# collection.net
KiCad netlist of a schematic drawn in Altium Designer
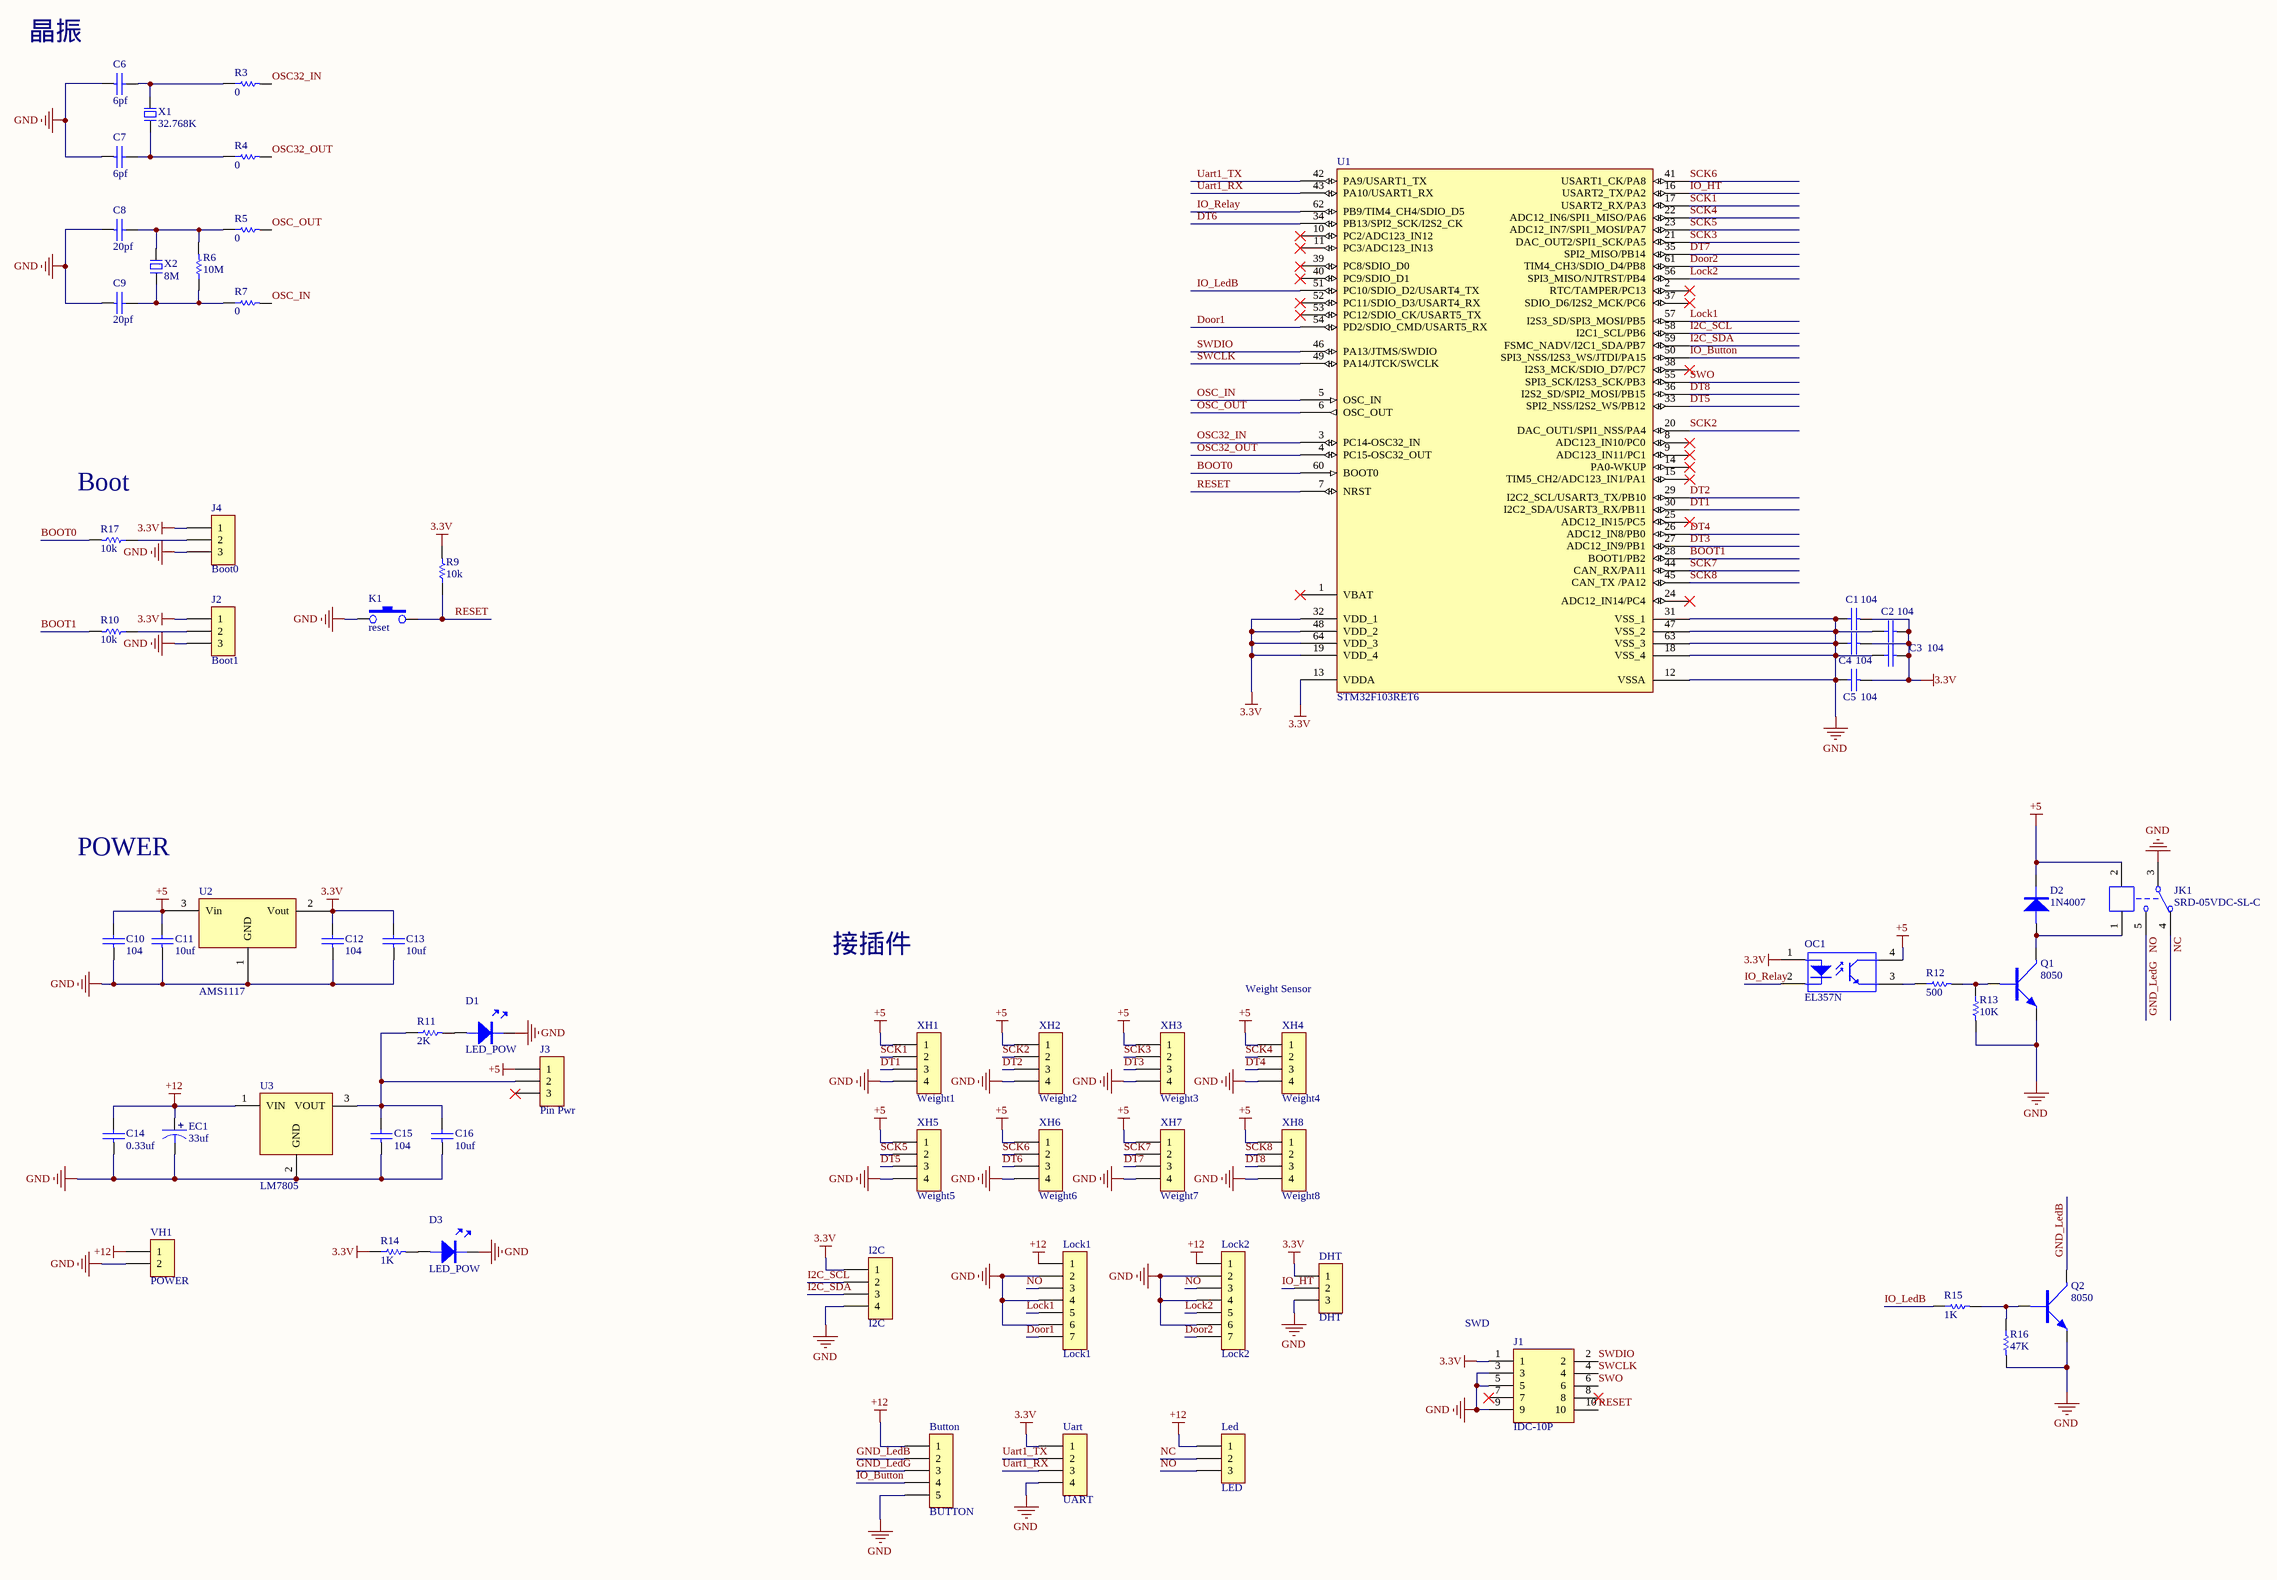
[diagram p0: collection.SchDoc]

(export (version "E")
  (design (tool "Eeschema 10.0.6"))
  (components
    (comp (ref "Button") (value "BUTTON") (footprint "XH5/2.54mm/90") (libsource (lib "XH，VH") (part "XH5")))
    (comp (ref "C1")
      (value "104")
      (footprint "0603C")
      (description "无极性电容")
      (libsource (lib "电容") (part "CAP"))
    )
    (comp (ref "C2")
      (value "104")
      (footprint "0603C")
      (description "无极性电容")
      (libsource (lib "电容") (part "CAP"))
    )
    (comp (ref "C3")
      (value "104")
      (footprint "0603C")
      (description "无极性电容")
      (libsource (lib "电容") (part "CAP"))
    )
    (comp (ref "C4")
      (value "104")
      (footprint "0603C")
      (description "无极性电容")
      (libsource (lib "电容") (part "CAP"))
    )
    (comp (ref "C5")
      (value "104")
      (footprint "0603C")
      (description "无极性电容")
      (libsource (lib "电容") (part "CAP"))
    )
    (comp (ref "C6")
      (value "6pf")
      (footprint "0603C")
      (description "无极性电容")
      (libsource (lib "电容") (part "CAP"))
    )
    (comp (ref "C7")
      (value "6pf")
      (footprint "0603C")
      (description "无极性电容")
      (libsource (lib "电容") (part "CAP"))
    )
    (comp (ref "C8")
      (value "20pf")
      (footprint "0603C")
      (description "无极性电容")
      (libsource (lib "电容") (part "CAP"))
    )
    (comp (ref "C9")
      (value "20pf")
      (footprint "0603C")
      (description "无极性电容")
      (libsource (lib "电容") (part "CAP"))
    )
    (comp (ref "C10")
      (value "104")
      (footprint "0805C")
      (description "无极性电容")
      (libsource (lib "电容") (part "CAP"))
    )
    (comp (ref "C11")
      (value "10uf")
      (footprint "0805C")
      (description "无极性电容")
      (libsource (lib "电容") (part "CAP"))
    )
    (comp (ref "C12")
      (value "104")
      (footprint "0805C")
      (description "无极性电容")
      (libsource (lib "电容") (part "CAP"))
    )
    (comp (ref "C13")
      (value "10uf")
      (footprint "0805C")
      (description "无极性电容")
      (libsource (lib "电容") (part "CAP"))
    )
    (comp (ref "C14")
      (value "0.33uf")
      (footprint "0805C")
      (description "无极性电容")
      (libsource (lib "电容") (part "CAP"))
    )
    (comp (ref "C15")
      (value "104")
      (footprint "0805C")
      (description "无极性电容")
      (libsource (lib "电容") (part "CAP"))
    )
    (comp (ref "C16")
      (value "10uf")
      (footprint "0805C")
      (description "无极性电容")
      (libsource (lib "电容") (part "CAP"))
    )
    (comp (ref "D1") (value "LED_POW") (footprint "LED-0805R") (libsource (lib "LED") (part "LED")))
    (comp (ref "D2")
      (value "1N4007")
      (footprint "SOD-123")
      (description "普通二极管")
      (libsource (lib "二极管") (part "DIODE"))
    )
    (comp (ref "D3") (value "LED_POW") (footprint "LED-0805G") (libsource (lib "LED") (part "LED")))
    (comp (ref "DHT") (value "DHT") (footprint "XH3/2.54mm/180") (libsource (lib "XH，VH") (part "XH3")))
    (comp (ref "EC1")
      (value "33uf")
      (footprint "SMD-EC6.3X6.3X10")
      (description "贴片电解电容")
      (libsource (lib "电容") (part "SMD_ECAP"))
    )
    (comp (ref "I2C") (value "I2C") (footprint "XH4/2.54mm/180") (libsource (lib "XH，VH") (part "XH4")))
    (comp (ref "J1") (value "IDC-10P") (footprint "IDC2.54-10P") (libsource (lib "简易牛角座") (part "IDC-10P")))
    (comp (ref "J2")
      (value "Boot1")
      (footprint "Pin HDR1X3/2.54mm-S")
      (libsource (lib "排针") (part "Pin HDR1X3"))
    )
    (comp (ref "J3")
      (value "Pin Pwr")
      (footprint "Pin HDR1X3/2.54mm-S")
      (libsource (lib "排针") (part "Pin HDR1X3"))
    )
    (comp (ref "J4")
      (value "Boot0")
      (footprint "Pin HDR1X3/2.54mm-S")
      (libsource (lib "排针") (part "Pin HDR1X3"))
    )
    (comp (ref "JK1")
      (value "SRD-05VDC-SL-C")
      (footprint "SRD-C_B")
      (description "5V一组转换")
      (libsource (lib "继电器") (part "SRD-05VDC-SL-C"))
    )
    (comp (ref "K1") (value "reset") (footprint "SMD-3X6X2.5") (libsource (lib "轻触开关") (part "KEY")))
    (comp (ref "Led") (value "LED") (footprint "XH3/2.54mm/90") (libsource (lib "XH，VH") (part "XH3")))
    (comp (ref "Lock1") (value "Lock1") (footprint "XH7/2.54mm/90") (libsource (lib "XH，VH") (part "XH7")))
    (comp (ref "Lock2") (value "Lock2") (footprint "XH7/2.54mm/90") (libsource (lib "XH，VH") (part "XH7")))
    (comp (ref "OC1")
      (value "EL357N")
      (footprint "SMD_EL357N")
      (description "线性光耦")
      (libsource (lib "光电隔离器") (part "EL357N"))
    )
    (comp (ref "Q1")
      (value "8050")
      (footprint "SOT-23")
      (description "NPN三极管")
      (libsource (lib "三极管") (part "NPN"))
    )
    (comp (ref "Q2")
      (value "8050")
      (footprint "SOT-23")
      (description "NPN三极管")
      (libsource (lib "三极管") (part "NPN"))
    )
    (comp (ref "R3") (value "0") (footprint "0603R") (libsource (lib "电阻") (part "RES")))
    (comp (ref "R4") (value "0") (footprint "0603R") (libsource (lib "电阻") (part "RES")))
    (comp (ref "R5") (value "0") (footprint "0603R") (libsource (lib "电阻") (part "RES")))
    (comp (ref "R6") (value "10M") (footprint "0805R") (libsource (lib "电阻") (part "RES")))
    (comp (ref "R7") (value "0") (footprint "0603R") (libsource (lib "电阻") (part "RES")))
    (comp (ref "R9") (value "10k") (footprint "0805R") (libsource (lib "电阻") (part "RES")))
    (comp (ref "R10") (value "10k") (footprint "0805R") (libsource (lib "电阻") (part "RES")))
    (comp (ref "R11") (value "2K") (footprint "0805R") (libsource (lib "电阻") (part "RES")))
    (comp (ref "R12") (value "500") (footprint "0805R") (libsource (lib "电阻") (part "RES")))
    (comp (ref "R13") (value "10K") (footprint "0805R") (libsource (lib "电阻") (part "RES")))
    (comp (ref "R14") (value "1K") (footprint "0805R") (libsource (lib "电阻") (part "RES")))
    (comp (ref "R15") (value "1K") (footprint "0805R") (libsource (lib "电阻") (part "RES")))
    (comp (ref "R16") (value "47K") (footprint "0805R") (libsource (lib "电阻") (part "RES")))
    (comp (ref "R17") (value "10k") (footprint "0805R") (libsource (lib "电阻") (part "RES")))
    (comp (ref "U1")
      (value "STM32F103RET6")
      (footprint "LQFP64 10x10")
      (libsource (lib "STM32系列") (part "STM32F103RET6"))
    )
    (comp (ref "U2")
      (value "AMS1117")
      (footprint "SOT223")
      (description "三端稳压芯片")
      (libsource (lib "电源芯片") (part "AMS1117"))
    )
    (comp (ref "U3") (value "LM7805") (footprint "TO252") (libsource (lib "电源芯片") (part "LM7805")))
    (comp (ref "Uart") (value "UART") (footprint "XH4/2.54mm/180") (libsource (lib "XH，VH") (part "XH4")))
    (comp (ref "VH1") (value "POWER") (footprint "VH3.96-2AW") (libsource (lib "XH，VH") (part "VH2")))
    (comp (ref "X1")
      (value "32.768K")
      (footprint "OSC-3x8-WI-B")
      (description "2脚无源脚晶振")
      (libsource (lib "晶振") (part "XTAL-2P"))
    )
    (comp (ref "X2")
      (value "8M")
      (footprint "OSC HC-49S")
      (description "2脚无源脚晶振")
      (libsource (lib "晶振") (part "XTAL-2P"))
    )
    (comp (ref "XH1") (value "Weight1") (footprint "XH4/2.54mm/180") (libsource (lib "XH，VH") (part "XH4")))
    (comp (ref "XH2") (value "Weight2") (footprint "XH4/2.54mm/180") (libsource (lib "XH，VH") (part "XH4")))
    (comp (ref "XH3") (value "Weight3") (footprint "XH4/2.54mm/180") (libsource (lib "XH，VH") (part "XH4")))
    (comp (ref "XH4") (value "Weight4") (footprint "XH4/2.54mm/180") (libsource (lib "XH，VH") (part "XH4")))
    (comp (ref "XH5") (value "Weight5") (footprint "XH4/2.54mm/180") (libsource (lib "XH，VH") (part "XH4")))
    (comp (ref "XH6") (value "Weight6") (footprint "XH4/2.54mm/180") (libsource (lib "XH，VH") (part "XH4")))
    (comp (ref "XH7") (value "Weight7") (footprint "XH4/2.54mm/180") (libsource (lib "XH，VH") (part "XH4")))
    (comp (ref "XH8") (value "Weight8") (footprint "XH4/2.54mm/180") (libsource (lib "XH，VH") (part "XH4")))
  )
  (nets
    (net (code "1") (name "+5") (class "Default")
      (node (ref "C10") (pin "2") (pinfunction "2_2") (pintype "passive"))
      (node (ref "C11") (pin "2") (pinfunction "2_2") (pintype "passive"))
      (node (ref "D2") (pin "K") (pinfunction "K_K") (pintype "passive"))
      (node (ref "J3") (pin "1") (pinfunction "1_1") (pintype "passive"))
      (node (ref "JK1") (pin "2") (pinfunction "2_2") (pintype "passive"))
      (node (ref "OC1") (pin "4") (pinfunction "C_4") (pintype "passive"))
      (node (ref "U2") (pin "3") (pinfunction "Vin_3") (pintype "passive"))
      (node (ref "XH1") (pin "1") (pinfunction "1_1") (pintype "passive"))
      (node (ref "XH2") (pin "1") (pinfunction "1_1") (pintype "passive"))
      (node (ref "XH3") (pin "1") (pinfunction "1_1") (pintype "passive"))
      (node (ref "XH4") (pin "1") (pinfunction "1_1") (pintype "passive"))
      (node (ref "XH5") (pin "1") (pinfunction "1_1") (pintype "passive"))
      (node (ref "XH6") (pin "1") (pinfunction "1_1") (pintype "passive"))
      (node (ref "XH7") (pin "1") (pinfunction "1_1") (pintype "passive"))
      (node (ref "XH8") (pin "1") (pinfunction "1_1") (pintype "passive"))
    )
    (net (code "2") (name "+12") (class "Default")
      (node (ref "Button") (pin "1") (pinfunction "1_1") (pintype "passive"))
      (node (ref "C14") (pin "2") (pinfunction "2_2") (pintype "passive"))
      (node (ref "EC1") (pin "1") (pinfunction "1_1") (pintype "passive"))
      (node (ref "Led") (pin "1") (pinfunction "1_1") (pintype "passive"))
      (node (ref "Lock1") (pin "1") (pinfunction "1_1") (pintype "passive"))
      (node (ref "Lock2") (pin "1") (pinfunction "1_1") (pintype "passive"))
      (node (ref "U3") (pin "1") (pinfunction "VIN_1") (pintype "passive"))
      (node (ref "VH1") (pin "1") (pinfunction "1_1") (pintype "passive"))
    )
    (net (code "3") (name "/BOOT0") (class "Default")
      (node (ref "R17") (pin "2") (pinfunction "2_2") (pintype "passive"))
      (node (ref "U1") (pin "60") (pinfunction "BOOT0_60") (pintype "input"))
    )
    (net (code "4") (name "/BOOT1") (class "Default")
      (node (ref "R10") (pin "2") (pinfunction "2_2") (pintype "passive"))
      (node (ref "U1") (pin "28") (pinfunction "BOOT1/PB2_28") (pintype "bidirectional"))
    )
    (net (code "5") (name "/DT1") (class "Default")
      (node (ref "U1") (pin "30") (pinfunction "I2C2_SDA/USART3_RX/PB11_30") (pintype "bidirectional"))
      (node (ref "XH1") (pin "3") (pinfunction "3_3") (pintype "passive"))
    )
    (net (code "6") (name "/DT2") (class "Default")
      (node (ref "U1") (pin "29") (pinfunction "I2C2_SCL/USART3_TX/PB10_29") (pintype "bidirectional"))
      (node (ref "XH2") (pin "3") (pinfunction "3_3") (pintype "passive"))
    )
    (net (code "7") (name "/DT3") (class "Default")
      (node (ref "U1") (pin "27") (pinfunction "ADC12_IN9/PB1_27") (pintype "bidirectional"))
      (node (ref "XH3") (pin "3") (pinfunction "3_3") (pintype "passive"))
    )
    (net (code "8") (name "/DT4") (class "Default")
      (node (ref "U1") (pin "26") (pinfunction "ADC12_IN8/PB0_26") (pintype "bidirectional"))
      (node (ref "XH4") (pin "3") (pinfunction "3_3") (pintype "passive"))
    )
    (net (code "9") (name "/DT5") (class "Default")
      (node (ref "U1") (pin "33") (pinfunction "SPI2_NSS/I2S2_WS/PB12_33") (pintype "bidirectional"))
      (node (ref "XH5") (pin "3") (pinfunction "3_3") (pintype "passive"))
    )
    (net (code "10") (name "/DT6") (class "Default")
      (node (ref "U1") (pin "34") (pinfunction "PB13/SPI2_SCK/I2S2_CK_34") (pintype "bidirectional"))
      (node (ref "XH6") (pin "3") (pinfunction "3_3") (pintype "passive"))
    )
    (net (code "11") (name "/DT7") (class "Default")
      (node (ref "U1") (pin "35") (pinfunction "SPI2_MISO/PB14_35") (pintype "bidirectional"))
      (node (ref "XH7") (pin "3") (pinfunction "3_3") (pintype "passive"))
    )
    (net (code "12") (name "/DT8") (class "Default")
      (node (ref "U1") (pin "36") (pinfunction "I2S2_SD/SPI2_MOSI/PB15_36") (pintype "bidirectional"))
      (node (ref "XH8") (pin "3") (pinfunction "3_3") (pintype "passive"))
    )
    (net (code "13") (name "/Door1") (class "Default")
      (node (ref "Lock1") (pin "7") (pinfunction "7_7") (pintype "passive"))
      (node (ref "U1") (pin "54") (pinfunction "PD2/SDIO_CMD/USART5_RX_54") (pintype "bidirectional"))
    )
    (net (code "14") (name "/Door2") (class "Default")
      (node (ref "Lock2") (pin "7") (pinfunction "7_7") (pintype "passive"))
      (node (ref "U1") (pin "61") (pinfunction "TIM4_CH3/SDIO_D4/PB8_61") (pintype "bidirectional"))
    )
    (net (code "15") (name "/GND_LedB") (class "Default")
      (node (ref "Button") (pin "2") (pinfunction "2_2") (pintype "passive"))
      (node (ref "Q2") (pin "C") (pinfunction "C_C") (pintype "passive"))
    )
    (net (code "16") (name "/GND_LedG") (class "Default")
      (node (ref "Button") (pin "3") (pinfunction "3_3") (pintype "passive"))
      (node (ref "JK1") (pin "5") (pinfunction "5_5") (pintype "passive"))
      (node (ref "Led") (pin "3") (pinfunction "3_3") (pintype "passive"))
      (node (ref "Lock1") (pin "3") (pinfunction "3_3") (pintype "passive"))
      (node (ref "Lock2") (pin "3") (pinfunction "3_3") (pintype "passive"))
    )
    (net (code "17") (name "/I2C_SCL") (class "Default")
      (node (ref "I2C") (pin "2") (pinfunction "2_2") (pintype "passive"))
      (node (ref "U1") (pin "58") (pinfunction "I2C1_SCL/PB6_58") (pintype "bidirectional"))
    )
    (net (code "18") (name "/I2C_SDA") (class "Default")
      (node (ref "I2C") (pin "3") (pinfunction "3_3") (pintype "passive"))
      (node (ref "U1") (pin "59") (pinfunction "FSMC_NADV/I2C1_SDA/PB7_59") (pintype "bidirectional"))
    )
    (net (code "19") (name "/IO_Button") (class "Default")
      (node (ref "Button") (pin "4") (pinfunction "4_4") (pintype "passive"))
      (node (ref "U1") (pin "50") (pinfunction "SPI3_NSS/I2S3_WS/JTDI/PA15_50") (pintype "bidirectional"))
    )
    (net (code "20") (name "/IO_HT") (class "Default")
      (node (ref "DHT") (pin "2") (pinfunction "2_2") (pintype "passive"))
      (node (ref "U1") (pin "16") (pinfunction "USART2_TX/PA2_16") (pintype "bidirectional"))
    )
    (net (code "21") (name "/IO_LedB") (class "Default")
      (node (ref "R15") (pin "1") (pinfunction "1_1") (pintype "passive"))
      (node (ref "U1") (pin "51") (pinfunction "PC10/SDIO_D2/USART4_TX_51") (pintype "bidirectional"))
    )
    (net (code "22") (name "/IO_Relay") (class "Default")
      (node (ref "OC1") (pin "2") (pinfunction "K_2") (pintype "passive"))
      (node (ref "U1") (pin "62") (pinfunction "PB9/TIM4_CH4/SDIO_D5_62") (pintype "bidirectional"))
    )
    (net (code "23") (name "/Lock1") (class "Default")
      (node (ref "Lock1") (pin "5") (pinfunction "5_5") (pintype "passive"))
      (node (ref "U1") (pin "57") (pinfunction "I2S3_SD/SPI3_MOSI/PB5_57") (pintype "bidirectional"))
    )
    (net (code "24") (name "/Lock2") (class "Default")
      (node (ref "Lock2") (pin "5") (pinfunction "5_5") (pintype "passive"))
      (node (ref "U1") (pin "56") (pinfunction "SPI3_MISO/NJTRST/PB4_56") (pintype "bidirectional"))
    )
    (net (code "25") (name "/NC") (class "Default")
      (node (ref "JK1") (pin "4") (pinfunction "4_4") (pintype "passive"))
      (node (ref "Led") (pin "2") (pinfunction "2_2") (pintype "passive"))
    )
    (net (code "26") (name "/OSC32_IN") (class "Default")
      (node (ref "R3") (pin "2") (pinfunction "2_2") (pintype "passive"))
      (node (ref "U1") (pin "3") (pinfunction "PC14-OSC32_IN_3") (pintype "bidirectional"))
    )
    (net (code "27") (name "/OSC32_OUT") (class "Default")
      (node (ref "R4") (pin "2") (pinfunction "2_2") (pintype "passive"))
      (node (ref "U1") (pin "4") (pinfunction "PC15-OSC32_OUT_4") (pintype "bidirectional"))
    )
    (net (code "28") (name "/OSC_IN") (class "Default")
      (node (ref "R7") (pin "2") (pinfunction "2_2") (pintype "passive"))
      (node (ref "U1") (pin "5") (pinfunction "OSC_IN_5") (pintype "input"))
    )
    (net (code "29") (name "/OSC_OUT") (class "Default")
      (node (ref "R5") (pin "2") (pinfunction "2_2") (pintype "passive"))
      (node (ref "U1") (pin "6") (pinfunction "OSC_OUT_6") (pintype "output"))
    )
    (net (code "30") (name "/RESET") (class "Default")
      (node (ref "J1") (pin "10") (pinfunction "10_10") (pintype "passive"))
      (node (ref "K1") (pin "3") (pinfunction "3_3") (pintype "passive"))
      (node (ref "R9") (pin "1") (pinfunction "1_1") (pintype "passive"))
      (node (ref "U1") (pin "7") (pinfunction "NRST_7") (pintype "bidirectional"))
    )
    (net (code "31") (name "/SCK1") (class "Default")
      (node (ref "U1") (pin "17") (pinfunction "USART2_RX/PA3_17") (pintype "bidirectional"))
      (node (ref "XH1") (pin "2") (pinfunction "2_2") (pintype "passive"))
    )
    (net (code "32") (name "/SCK2") (class "Default")
      (node (ref "U1") (pin "20") (pinfunction "DAC_OUT1/SPI1_NSS/PA4_20") (pintype "bidirectional"))
      (node (ref "XH2") (pin "2") (pinfunction "2_2") (pintype "passive"))
    )
    (net (code "33") (name "/SCK3") (class "Default")
      (node (ref "U1") (pin "21") (pinfunction "DAC_OUT2/SPI1_SCK/PA5_21") (pintype "bidirectional"))
      (node (ref "XH3") (pin "2") (pinfunction "2_2") (pintype "passive"))
    )
    (net (code "34") (name "/SCK4") (class "Default")
      (node (ref "U1") (pin "22") (pinfunction "ADC12_IN6/SPI1_MISO/PA6_22") (pintype "bidirectional"))
      (node (ref "XH4") (pin "2") (pinfunction "2_2") (pintype "passive"))
    )
    (net (code "35") (name "/SCK5") (class "Default")
      (node (ref "U1") (pin "23") (pinfunction "ADC12_IN7/SPI1_MOSI/PA7_23") (pintype "bidirectional"))
      (node (ref "XH5") (pin "2") (pinfunction "2_2") (pintype "passive"))
    )
    (net (code "36") (name "/SCK6") (class "Default")
      (node (ref "U1") (pin "41") (pinfunction "USART1_CK/PA8_41") (pintype "bidirectional"))
      (node (ref "XH6") (pin "2") (pinfunction "2_2") (pintype "passive"))
    )
    (net (code "37") (name "/SCK7") (class "Default")
      (node (ref "U1") (pin "44") (pinfunction "CAN_RX/PA11_44") (pintype "bidirectional"))
      (node (ref "XH7") (pin "2") (pinfunction "2_2") (pintype "passive"))
    )
    (net (code "38") (name "/SCK8") (class "Default")
      (node (ref "U1") (pin "45") (pinfunction "CAN_TX_/PA12_45") (pintype "bidirectional"))
      (node (ref "XH8") (pin "2") (pinfunction "2_2") (pintype "passive"))
    )
    (net (code "39") (name "/SWCLK") (class "Default")
      (node (ref "J1") (pin "4") (pinfunction "4_4") (pintype "passive"))
      (node (ref "U1") (pin "49") (pinfunction "PA14/JTCK/SWCLK_49") (pintype "bidirectional"))
    )
    (net (code "40") (name "/SWDIO") (class "Default")
      (node (ref "J1") (pin "2") (pinfunction "2_2") (pintype "passive"))
      (node (ref "U1") (pin "46") (pinfunction "PA13/JTMS/SWDIO_46") (pintype "bidirectional"))
    )
    (net (code "41") (name "/SWO") (class "Default")
      (node (ref "J1") (pin "6") (pinfunction "6_6") (pintype "passive"))
      (node (ref "U1") (pin "55") (pinfunction "SPI3_SCK/I2S3_SCK/PB3_55") (pintype "bidirectional"))
    )
    (net (code "42") (name "/Uart1_RX") (class "Default")
      (node (ref "U1") (pin "43") (pinfunction "PA10/USART1_RX_43") (pintype "bidirectional"))
      (node (ref "Uart") (pin "3") (pinfunction "3_3") (pintype "passive"))
    )
    (net (code "43") (name "/Uart1_TX") (class "Default")
      (node (ref "U1") (pin "42") (pinfunction "PA9/USART1_TX_42") (pintype "bidirectional"))
      (node (ref "Uart") (pin "2") (pinfunction "2_2") (pintype "passive"))
    )
    (net (code "44") (name "3.3V") (class "Default")
      (node (ref "C1") (pin "1") (pinfunction "1_1") (pintype "passive"))
      (node (ref "C12") (pin "2") (pinfunction "2_2") (pintype "passive"))
      (node (ref "C13") (pin "2") (pinfunction "2_2") (pintype "passive"))
      (node (ref "C2") (pin "1") (pinfunction "1_1") (pintype "passive"))
      (node (ref "C3") (pin "1") (pinfunction "1_1") (pintype "passive"))
      (node (ref "C4") (pin "1") (pinfunction "1_1") (pintype "passive"))
      (node (ref "C5") (pin "1") (pinfunction "1_1") (pintype "passive"))
      (node (ref "DHT") (pin "1") (pinfunction "1_1") (pintype "passive"))
      (node (ref "I2C") (pin "1") (pinfunction "1_1") (pintype "passive"))
      (node (ref "J1") (pin "1") (pinfunction "1_1") (pintype "passive"))
      (node (ref "J2") (pin "1") (pinfunction "1_1") (pintype "passive"))
      (node (ref "J4") (pin "1") (pinfunction "1_1") (pintype "passive"))
      (node (ref "OC1") (pin "1") (pinfunction "A_1") (pintype "passive"))
      (node (ref "R14") (pin "1") (pinfunction "1_1") (pintype "passive"))
      (node (ref "R9") (pin "2") (pinfunction "2_2") (pintype "passive"))
      (node (ref "U1") (pin "13") (pinfunction "VDDA_13") (pintype "power_in"))
      (node (ref "U1") (pin "19") (pinfunction "VDD_4_19") (pintype "power_in"))
      (node (ref "U1") (pin "32") (pinfunction "VDD_1_32") (pintype "power_in"))
      (node (ref "U1") (pin "48") (pinfunction "VDD_2_48") (pintype "power_in"))
      (node (ref "U1") (pin "64") (pinfunction "VDD_3_64") (pintype "power_in"))
      (node (ref "U2") (pin "2") (pinfunction "Vout_2") (pintype "passive"))
      (node (ref "Uart") (pin "1") (pinfunction "1_1") (pintype "passive"))
    )
    (net (code "45") (name "GND") (class "Default")
      (node (ref "Button") (pin "5") (pinfunction "5_5") (pintype "passive"))
      (node (ref "C1") (pin "2") (pinfunction "2_2") (pintype "passive"))
      (node (ref "C10") (pin "1") (pinfunction "1_1") (pintype "passive"))
      (node (ref "C11") (pin "1") (pinfunction "1_1") (pintype "passive"))
      (node (ref "C12") (pin "1") (pinfunction "1_1") (pintype "passive"))
      (node (ref "C13") (pin "1") (pinfunction "1_1") (pintype "passive"))
      (node (ref "C14") (pin "1") (pinfunction "1_1") (pintype "passive"))
      (node (ref "C15") (pin "1") (pinfunction "1_1") (pintype "passive"))
      (node (ref "C16") (pin "1") (pinfunction "1_1") (pintype "passive"))
      (node (ref "C2") (pin "2") (pinfunction "2_2") (pintype "passive"))
      (node (ref "C3") (pin "2") (pinfunction "2_2") (pintype "passive"))
      (node (ref "C4") (pin "2") (pinfunction "2_2") (pintype "passive"))
      (node (ref "C5") (pin "2") (pinfunction "2_2") (pintype "passive"))
      (node (ref "C6") (pin "1") (pinfunction "1_1") (pintype "passive"))
      (node (ref "C7") (pin "1") (pinfunction "1_1") (pintype "passive"))
      (node (ref "C8") (pin "1") (pinfunction "1_1") (pintype "passive"))
      (node (ref "C9") (pin "1") (pinfunction "1_1") (pintype "passive"))
      (node (ref "D1") (pin "K") (pinfunction "K_K") (pintype "passive"))
      (node (ref "D3") (pin "K") (pinfunction "K_K") (pintype "passive"))
      (node (ref "DHT") (pin "3") (pinfunction "3_3") (pintype "passive"))
      (node (ref "EC1") (pin "2") (pinfunction "2_2") (pintype "passive"))
      (node (ref "I2C") (pin "4") (pinfunction "4_4") (pintype "passive"))
      (node (ref "J1") (pin "3") (pinfunction "3_3") (pintype "passive"))
      (node (ref "J1") (pin "5") (pinfunction "5_5") (pintype "passive"))
      (node (ref "J1") (pin "9") (pinfunction "9_9") (pintype "passive"))
      (node (ref "J2") (pin "3") (pinfunction "3_3") (pintype "passive"))
      (node (ref "J4") (pin "3") (pinfunction "3_3") (pintype "passive"))
      (node (ref "JK1") (pin "3") (pinfunction "3_3") (pintype "passive"))
      (node (ref "K1") (pin "1") (pinfunction "1_1") (pintype "passive"))
      (node (ref "Lock1") (pin "2") (pinfunction "2_2") (pintype "passive"))
      (node (ref "Lock1") (pin "4") (pinfunction "4_4") (pintype "passive"))
      (node (ref "Lock1") (pin "6") (pinfunction "6_6") (pintype "passive"))
      (node (ref "Lock2") (pin "2") (pinfunction "2_2") (pintype "passive"))
      (node (ref "Lock2") (pin "4") (pinfunction "4_4") (pintype "passive"))
      (node (ref "Lock2") (pin "6") (pinfunction "6_6") (pintype "passive"))
      (node (ref "Q1") (pin "E") (pinfunction "E_E") (pintype "passive"))
      (node (ref "Q2") (pin "E") (pinfunction "E_E") (pintype "passive"))
      (node (ref "R13") (pin "2") (pinfunction "2_2") (pintype "passive"))
      (node (ref "R16") (pin "2") (pinfunction "2_2") (pintype "passive"))
      (node (ref "U1") (pin "12") (pinfunction "VSSA_12") (pintype "power_in"))
      (node (ref "U1") (pin "18") (pinfunction "VSS_4_18") (pintype "power_in"))
      (node (ref "U1") (pin "31") (pinfunction "VSS_1_31") (pintype "passive"))
      (node (ref "U1") (pin "47") (pinfunction "VSS_2_47") (pintype "passive"))
      (node (ref "U1") (pin "63") (pinfunction "VSS_3_63") (pintype "power_in"))
      (node (ref "U2") (pin "1") (pinfunction "GND_1") (pintype "passive"))
      (node (ref "U3") (pin "2") (pinfunction "GND_2") (pintype "passive"))
      (node (ref "Uart") (pin "4") (pinfunction "4_4") (pintype "passive"))
      (node (ref "VH1") (pin "2") (pinfunction "2_2") (pintype "passive"))
      (node (ref "XH1") (pin "4") (pinfunction "4_4") (pintype "passive"))
      (node (ref "XH2") (pin "4") (pinfunction "4_4") (pintype "passive"))
      (node (ref "XH3") (pin "4") (pinfunction "4_4") (pintype "passive"))
      (node (ref "XH4") (pin "4") (pinfunction "4_4") (pintype "passive"))
      (node (ref "XH5") (pin "4") (pinfunction "4_4") (pintype "passive"))
      (node (ref "XH6") (pin "4") (pinfunction "4_4") (pintype "passive"))
      (node (ref "XH7") (pin "4") (pinfunction "4_4") (pintype "passive"))
      (node (ref "XH8") (pin "4") (pinfunction "4_4") (pintype "passive"))
    )
    (net (code "46") (name "Net-(C6-Pad2)") (class "Default")
      (node (ref "C6") (pin "2") (pinfunction "2_2") (pintype "passive"))
      (node (ref "R3") (pin "1") (pinfunction "1_1") (pintype "passive"))
      (node (ref "X1") (pin "2") (pinfunction "2_2") (pintype "passive"))
    )
    (net (code "47") (name "Net-(C7-Pad2)") (class "Default")
      (node (ref "C7") (pin "2") (pinfunction "2_2") (pintype "passive"))
      (node (ref "R4") (pin "1") (pinfunction "1_1") (pintype "passive"))
      (node (ref "X1") (pin "1") (pinfunction "1_1") (pintype "passive"))
    )
    (net (code "48") (name "Net-(C8-Pad2)") (class "Default")
      (node (ref "C8") (pin "2") (pinfunction "2_2") (pintype "passive"))
      (node (ref "R5") (pin "1") (pinfunction "1_1") (pintype "passive"))
      (node (ref "R6") (pin "2") (pinfunction "2_2") (pintype "passive"))
      (node (ref "X2") (pin "2") (pinfunction "2_2") (pintype "passive"))
    )
    (net (code "49") (name "Net-(C9-Pad2)") (class "Default")
      (node (ref "C9") (pin "2") (pinfunction "2_2") (pintype "passive"))
      (node (ref "R6") (pin "1") (pinfunction "1_1") (pintype "passive"))
      (node (ref "R7") (pin "1") (pinfunction "1_1") (pintype "passive"))
      (node (ref "X2") (pin "1") (pinfunction "1_1") (pintype "passive"))
    )
    (net (code "50") (name "Net-(D1-PadA)") (class "Default")
      (node (ref "D1") (pin "A") (pinfunction "A_A") (pintype "passive"))
      (node (ref "R11") (pin "2") (pinfunction "2_2") (pintype "passive"))
    )
    (net (code "51") (name "Net-(D2-PadA)") (class "Default")
      (node (ref "D2") (pin "A") (pinfunction "A_A") (pintype "passive"))
      (node (ref "JK1") (pin "1") (pinfunction "1_1") (pintype "passive"))
      (node (ref "Q1") (pin "C") (pinfunction "C_C") (pintype "passive"))
    )
    (net (code "52") (name "Net-(D3-PadA)") (class "Default")
      (node (ref "D3") (pin "A") (pinfunction "A_A") (pintype "passive"))
      (node (ref "R14") (pin "2") (pinfunction "2_2") (pintype "passive"))
    )
    (net (code "53") (name "Net-(J2-Pad2)") (class "Default")
      (node (ref "J2") (pin "2") (pinfunction "2_2") (pintype "passive"))
      (node (ref "R10") (pin "1") (pinfunction "1_1") (pintype "passive"))
    )
    (net (code "54") (name "Net-(J4-Pad2)") (class "Default")
      (node (ref "J4") (pin "2") (pinfunction "2_2") (pintype "passive"))
      (node (ref "R17") (pin "1") (pinfunction "1_1") (pintype "passive"))
    )
    (net (code "55") (name "Net-(OC1-E)") (class "Default")
      (node (ref "OC1") (pin "3") (pinfunction "E_3") (pintype "passive"))
      (node (ref "R12") (pin "1") (pinfunction "1_1") (pintype "passive"))
    )
    (net (code "56") (name "Net-(Q1-PadB)") (class "Default")
      (node (ref "Q1") (pin "B") (pinfunction "B_B") (pintype "passive"))
      (node (ref "R12") (pin "2") (pinfunction "2_2") (pintype "passive"))
      (node (ref "R13") (pin "1") (pinfunction "1_1") (pintype "passive"))
    )
    (net (code "57") (name "Net-(Q2-PadB)") (class "Default")
      (node (ref "Q2") (pin "B") (pinfunction "B_B") (pintype "passive"))
      (node (ref "R15") (pin "2") (pinfunction "2_2") (pintype "passive"))
      (node (ref "R16") (pin "1") (pinfunction "1_1") (pintype "passive"))
    )
    (net (code "58") (name "Net-(U3-VOUT)") (class "Default")
      (node (ref "C15") (pin "2") (pinfunction "2_2") (pintype "passive"))
      (node (ref "C16") (pin "2") (pinfunction "2_2") (pintype "passive"))
      (node (ref "J3") (pin "2") (pinfunction "2_2") (pintype "passive"))
      (node (ref "R11") (pin "1") (pinfunction "1_1") (pintype "passive"))
      (node (ref "U3") (pin "3") (pinfunction "VOUT_3") (pintype "passive"))
    )
    (net (code "59") (name "unconnected-(J1-Pad7)") (class "Default")
      (node (ref "J1") (pin "7") (pinfunction "7_7") (pintype "passive+no_connect"))
    )
    (net (code "60") (name "unconnected-(J1-Pad8)") (class "Default")
      (node (ref "J1") (pin "8") (pinfunction "8_8") (pintype "passive+no_connect"))
    )
    (net (code "61") (name "unconnected-(J3-Pad3)") (class "Default")
      (node (ref "J3") (pin "3") (pinfunction "3_3") (pintype "passive+no_connect"))
    )
    (net (code "62") (name "unconnected-(U1-ADC12_IN14{slash}PC4-Pad24)") (class "Default")
      (node (ref "U1") (pin "24") (pinfunction "ADC12_IN14/PC4_24") (pintype "bidirectional+no_connect"))
    )
    (net (code "63") (name "unconnected-(U1-ADC12_IN15{slash}PC5-Pad25)") (class "Default")
      (node (ref "U1") (pin "25") (pinfunction "ADC12_IN15/PC5_25") (pintype "bidirectional+no_connect"))
    )
    (net (code "64") (name "unconnected-(U1-ADC123_IN10{slash}PC0-Pad8)") (class "Default")
      (node (ref "U1") (pin "8") (pinfunction "ADC123_IN10/PC0_8") (pintype "bidirectional+no_connect"))
    )
    (net (code "65") (name "unconnected-(U1-ADC123_IN11{slash}PC1-Pad9)") (class "Default")
      (node (ref "U1") (pin "9") (pinfunction "ADC123_IN11/PC1_9") (pintype "bidirectional+no_connect"))
    )
    (net (code "66") (name "unconnected-(U1-I2S3_MCK{slash}SDIO_D7{slash}PC7-Pad38)") (class "Default")
      (node (ref "U1") (pin "38") (pinfunction "I2S3_MCK/SDIO_D7/PC7_38") (pintype "bidirectional+no_connect"))
    )
    (net (code "67") (name "unconnected-(U1-PA0-WKUP-Pad14)") (class "Default")
      (node (ref "U1") (pin "14") (pinfunction "PA0-WKUP_14") (pintype "bidirectional+no_connect"))
    )
    (net (code "68") (name "unconnected-(U1-PC2{slash}ADC123_IN12-Pad10)") (class "Default")
      (node (ref "U1") (pin "10") (pinfunction "PC2/ADC123_IN12_10") (pintype "bidirectional+no_connect"))
    )
    (net (code "69") (name "unconnected-(U1-PC3{slash}ADC123_IN13-Pad11)") (class "Default")
      (node (ref "U1") (pin "11") (pinfunction "PC3/ADC123_IN13_11") (pintype "bidirectional+no_connect"))
    )
    (net (code "70") (name "unconnected-(U1-PC8{slash}SDIO_D0-Pad39)") (class "Default")
      (node (ref "U1") (pin "39") (pinfunction "PC8/SDIO_D0_39") (pintype "bidirectional+no_connect"))
    )
    (net (code "71") (name "unconnected-(U1-PC9{slash}SDIO_D1-Pad40)") (class "Default")
      (node (ref "U1") (pin "40") (pinfunction "PC9/SDIO_D1_40") (pintype "bidirectional+no_connect"))
    )
    (net (code "72") (name "unconnected-(U1-PC11{slash}SDIO_D3{slash}USART4_RX-Pad52)") (class "Default")
      (node (ref "U1") (pin "52") (pinfunction "PC11/SDIO_D3/USART4_RX_52") (pintype "bidirectional+no_connect"))
    )
    (net (code "73") (name "unconnected-(U1-PC12{slash}SDIO_CK{slash}USART5_TX-Pad53)") (class "Default")
      (node (ref "U1") (pin "53") (pinfunction "PC12/SDIO_CK/USART5_TX_53") (pintype "bidirectional+no_connect"))
    )
    (net (code "74") (name "unconnected-(U1-RTC{slash}TAMPER{slash}PC13-Pad2)") (class "Default")
      (node (ref "U1") (pin "2") (pinfunction "RTC/TAMPER/PC13_2") (pintype "bidirectional+no_connect"))
    )
    (net (code "75") (name "unconnected-(U1-SDIO_D6{slash}I2S2_MCK{slash}PC6-Pad37)") (class "Default")
      (node (ref "U1") (pin "37") (pinfunction "SDIO_D6/I2S2_MCK/PC6_37") (pintype "bidirectional+no_connect"))
    )
    (net (code "76") (name "unconnected-(U1-TIM5_CH2{slash}ADC123_IN1{slash}PA1-Pad15)") (class "Default")
      (node (ref "U1") (pin "15") (pinfunction "TIM5_CH2/ADC123_IN1/PA1_15") (pintype "bidirectional+no_connect"))
    )
    (net (code "77") (name "unconnected-(U1-VBAT-Pad1)") (class "Default")
      (node (ref "U1") (pin "1") (pinfunction "VBAT_1") (pintype "power_in+no_connect"))
    )
  )
)
